# customLidar.net
KiCad netlist of a schematic drawn in EAGLE
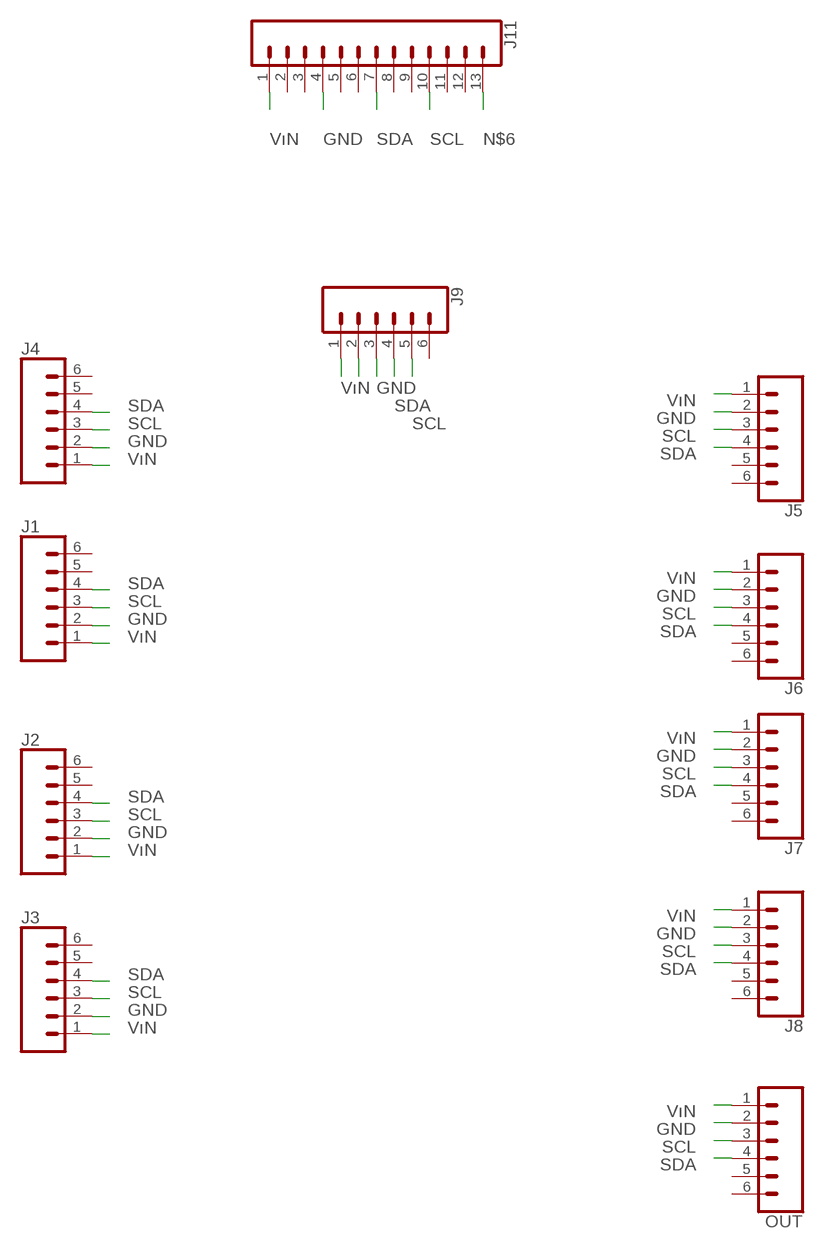
[diagram p0: schematic, sheet 1]

(export (version "E")
  (design (tool "Eeschema 10.0.6"))
  (components
    (comp (ref "J1")
      (value "CONN_06LONGPADS")
      (footprint "eagle-import:1X06_LONGPADS")
      (libsource (lib "eagle-import") (part "CONN_06LONGPADS"))
    )
    (comp (ref "J2")
      (value "CONN_06LONGPADS")
      (footprint "eagle-import:1X06_LONGPADS")
      (libsource (lib "eagle-import") (part "CONN_06LONGPADS"))
    )
    (comp (ref "J3")
      (value "CONN_06LONGPADS")
      (footprint "eagle-import:1X06_LONGPADS")
      (libsource (lib "eagle-import") (part "CONN_06LONGPADS"))
    )
    (comp (ref "J4")
      (value "CONN_06LONGPADS")
      (footprint "eagle-import:1X06_LONGPADS")
      (libsource (lib "eagle-import") (part "CONN_06LONGPADS"))
    )
    (comp (ref "J5")
      (value "CONN_06LONGPADS")
      (footprint "eagle-import:1X06_LONGPADS")
      (libsource (lib "eagle-import") (part "CONN_06LONGPADS"))
    )
    (comp (ref "J6")
      (value "CONN_06LONGPADS")
      (footprint "eagle-import:1X06_LONGPADS")
      (libsource (lib "eagle-import") (part "CONN_06LONGPADS"))
    )
    (comp (ref "J7")
      (value "CONN_06LONGPADS")
      (footprint "eagle-import:1X06_LONGPADS")
      (libsource (lib "eagle-import") (part "CONN_06LONGPADS"))
    )
    (comp (ref "J8")
      (value "CONN_06LONGPADS")
      (footprint "eagle-import:1X06_LONGPADS")
      (libsource (lib "eagle-import") (part "CONN_06LONGPADS"))
    )
    (comp (ref "J9")
      (value "CONN_06LONGPADS")
      (footprint "eagle-import:1X06_LONGPADS")
      (libsource (lib "eagle-import") (part "CONN_06LONGPADS"))
    )
    (comp (ref "J11")
      (value "CONN_13LONGPADS")
      (footprint "eagle-import:1X13-LONGPADS")
      (libsource (lib "eagle-import") (part "CONN_13LONGPADS"))
    )
    (comp (ref "OUT")
      (value "CONN_06LONGPADS")
      (footprint "eagle-import:1X06_LONGPADS")
      (libsource (lib "eagle-import") (part "CONN_06LONGPADS"))
    )
  )
  (nets
    (net (code "1") (name "/GND") (class "Default")
      (node (ref "J1") (pin "2") (pinfunction "2_2") (pintype "passive"))
      (node (ref "J11") (pin "4") (pinfunction "4_4") (pintype "passive"))
      (node (ref "J2") (pin "2") (pinfunction "2_2") (pintype "passive"))
      (node (ref "J3") (pin "2") (pinfunction "2_2") (pintype "passive"))
      (node (ref "J4") (pin "2") (pinfunction "2_2") (pintype "passive"))
      (node (ref "J5") (pin "2") (pinfunction "2_2") (pintype "passive"))
      (node (ref "J6") (pin "2") (pinfunction "2_2") (pintype "passive"))
      (node (ref "J7") (pin "2") (pinfunction "2_2") (pintype "passive"))
      (node (ref "J8") (pin "2") (pinfunction "2_2") (pintype "passive"))
      (node (ref "J9") (pin "3") (pinfunction "3_3") (pintype "passive"))
      (node (ref "OUT") (pin "2") (pinfunction "2_2") (pintype "passive"))
    )
    (net (code "2") (name "/N$6") (class "Default")
      (node (ref "J11") (pin "13") (pinfunction "13_13") (pintype "passive"))
    )
    (net (code "3") (name "/SCL") (class "Default")
      (node (ref "J1") (pin "3") (pinfunction "3_3") (pintype "passive"))
      (node (ref "J11") (pin "10") (pinfunction "10_10") (pintype "passive"))
      (node (ref "J2") (pin "3") (pinfunction "3_3") (pintype "passive"))
      (node (ref "J3") (pin "3") (pinfunction "3_3") (pintype "passive"))
      (node (ref "J4") (pin "3") (pinfunction "3_3") (pintype "passive"))
      (node (ref "J5") (pin "3") (pinfunction "3_3") (pintype "passive"))
      (node (ref "J6") (pin "3") (pinfunction "3_3") (pintype "passive"))
      (node (ref "J7") (pin "3") (pinfunction "3_3") (pintype "passive"))
      (node (ref "J8") (pin "3") (pinfunction "3_3") (pintype "passive"))
      (node (ref "J9") (pin "5") (pinfunction "5_5") (pintype "passive"))
      (node (ref "OUT") (pin "3") (pinfunction "3_3") (pintype "passive"))
    )
    (net (code "4") (name "/SDA") (class "Default")
      (node (ref "J1") (pin "4") (pinfunction "4_4") (pintype "passive"))
      (node (ref "J11") (pin "7") (pinfunction "7_7") (pintype "passive"))
      (node (ref "J2") (pin "4") (pinfunction "4_4") (pintype "passive"))
      (node (ref "J3") (pin "4") (pinfunction "4_4") (pintype "passive"))
      (node (ref "J4") (pin "4") (pinfunction "4_4") (pintype "passive"))
      (node (ref "J5") (pin "4") (pinfunction "4_4") (pintype "passive"))
      (node (ref "J6") (pin "4") (pinfunction "4_4") (pintype "passive"))
      (node (ref "J7") (pin "4") (pinfunction "4_4") (pintype "passive"))
      (node (ref "J8") (pin "4") (pinfunction "4_4") (pintype "passive"))
      (node (ref "J9") (pin "4") (pinfunction "4_4") (pintype "passive"))
      (node (ref "OUT") (pin "4") (pinfunction "4_4") (pintype "passive"))
    )
    (net (code "5") (name "/VıN") (class "Default")
      (node (ref "J1") (pin "1") (pinfunction "1_1") (pintype "passive"))
      (node (ref "J11") (pin "1") (pinfunction "1_1") (pintype "passive"))
      (node (ref "J2") (pin "1") (pinfunction "1_1") (pintype "passive"))
      (node (ref "J3") (pin "1") (pinfunction "1_1") (pintype "passive"))
      (node (ref "J4") (pin "1") (pinfunction "1_1") (pintype "passive"))
      (node (ref "J5") (pin "1") (pinfunction "1_1") (pintype "passive"))
      (node (ref "J6") (pin "1") (pinfunction "1_1") (pintype "passive"))
      (node (ref "J7") (pin "1") (pinfunction "1_1") (pintype "passive"))
      (node (ref "J8") (pin "1") (pinfunction "1_1") (pintype "passive"))
      (node (ref "J9") (pin "1") (pinfunction "1_1") (pintype "passive"))
      (node (ref "OUT") (pin "1") (pinfunction "1_1") (pintype "passive"))
    )
    (net (code "6") (name "unconnected-(J1-Pad5)") (class "Default")
      (node (ref "J1") (pin "5") (pinfunction "5_5") (pintype "passive"))
    )
    (net (code "7") (name "unconnected-(J1-Pad6)") (class "Default")
      (node (ref "J1") (pin "6") (pinfunction "6_6") (pintype "passive"))
    )
    (net (code "8") (name "unconnected-(J2-Pad5)") (class "Default")
      (node (ref "J2") (pin "5") (pinfunction "5_5") (pintype "passive"))
    )
    (net (code "9") (name "unconnected-(J2-Pad6)") (class "Default")
      (node (ref "J2") (pin "6") (pinfunction "6_6") (pintype "passive"))
    )
    (net (code "10") (name "unconnected-(J3-Pad5)") (class "Default")
      (node (ref "J3") (pin "5") (pinfunction "5_5") (pintype "passive"))
    )
    (net (code "11") (name "unconnected-(J3-Pad6)") (class "Default")
      (node (ref "J3") (pin "6") (pinfunction "6_6") (pintype "passive"))
    )
    (net (code "12") (name "unconnected-(J4-Pad5)") (class "Default")
      (node (ref "J4") (pin "5") (pinfunction "5_5") (pintype "passive"))
    )
    (net (code "13") (name "unconnected-(J4-Pad6)") (class "Default")
      (node (ref "J4") (pin "6") (pinfunction "6_6") (pintype "passive"))
    )
    (net (code "14") (name "unconnected-(J5-Pad5)") (class "Default")
      (node (ref "J5") (pin "5") (pinfunction "5_5") (pintype "passive"))
    )
    (net (code "15") (name "unconnected-(J5-Pad6)") (class "Default")
      (node (ref "J5") (pin "6") (pinfunction "6_6") (pintype "passive"))
    )
    (net (code "16") (name "unconnected-(J6-Pad5)") (class "Default")
      (node (ref "J6") (pin "5") (pinfunction "5_5") (pintype "passive"))
    )
    (net (code "17") (name "unconnected-(J6-Pad6)") (class "Default")
      (node (ref "J6") (pin "6") (pinfunction "6_6") (pintype "passive"))
    )
    (net (code "18") (name "unconnected-(J7-Pad5)") (class "Default")
      (node (ref "J7") (pin "5") (pinfunction "5_5") (pintype "passive"))
    )
    (net (code "19") (name "unconnected-(J7-Pad6)") (class "Default")
      (node (ref "J7") (pin "6") (pinfunction "6_6") (pintype "passive"))
    )
    (net (code "20") (name "unconnected-(J8-Pad5)") (class "Default")
      (node (ref "J8") (pin "5") (pinfunction "5_5") (pintype "passive"))
    )
    (net (code "21") (name "unconnected-(J8-Pad6)") (class "Default")
      (node (ref "J8") (pin "6") (pinfunction "6_6") (pintype "passive"))
    )
    (net (code "22") (name "unconnected-(J9-Pad2)") (class "Default")
      (node (ref "J9") (pin "2") (pinfunction "2_2") (pintype "passive"))
    )
    (net (code "23") (name "unconnected-(J9-Pad6)") (class "Default")
      (node (ref "J9") (pin "6") (pinfunction "6_6") (pintype "passive"))
    )
    (net (code "24") (name "unconnected-(J11-Pad2)") (class "Default")
      (node (ref "J11") (pin "2") (pinfunction "2_2") (pintype "passive"))
    )
    (net (code "25") (name "unconnected-(J11-Pad3)") (class "Default")
      (node (ref "J11") (pin "3") (pinfunction "3_3") (pintype "passive"))
    )
    (net (code "26") (name "unconnected-(J11-Pad5)") (class "Default")
      (node (ref "J11") (pin "5") (pinfunction "5_5") (pintype "passive"))
    )
    (net (code "27") (name "unconnected-(J11-Pad6)") (class "Default")
      (node (ref "J11") (pin "6") (pinfunction "6_6") (pintype "passive"))
    )
    (net (code "28") (name "unconnected-(J11-Pad8)") (class "Default")
      (node (ref "J11") (pin "8") (pinfunction "8_8") (pintype "passive"))
    )
    (net (code "29") (name "unconnected-(J11-Pad9)") (class "Default")
      (node (ref "J11") (pin "9") (pinfunction "9_9") (pintype "passive"))
    )
    (net (code "30") (name "unconnected-(J11-Pad11)") (class "Default")
      (node (ref "J11") (pin "11") (pinfunction "11_11") (pintype "passive"))
    )
    (net (code "31") (name "unconnected-(J11-Pad12)") (class "Default")
      (node (ref "J11") (pin "12") (pinfunction "12_12") (pintype "passive"))
    )
    (net (code "32") (name "unconnected-(OUT-Pad5)") (class "Default")
      (node (ref "OUT") (pin "5") (pinfunction "5_5") (pintype "passive"))
    )
    (net (code "33") (name "unconnected-(OUT-Pad6)") (class "Default")
      (node (ref "OUT") (pin "6") (pinfunction "6_6") (pintype "passive"))
    )
  )
)
